# central_sensoresv7.net
KiCad netlist of a schematic drawn in EAGLE
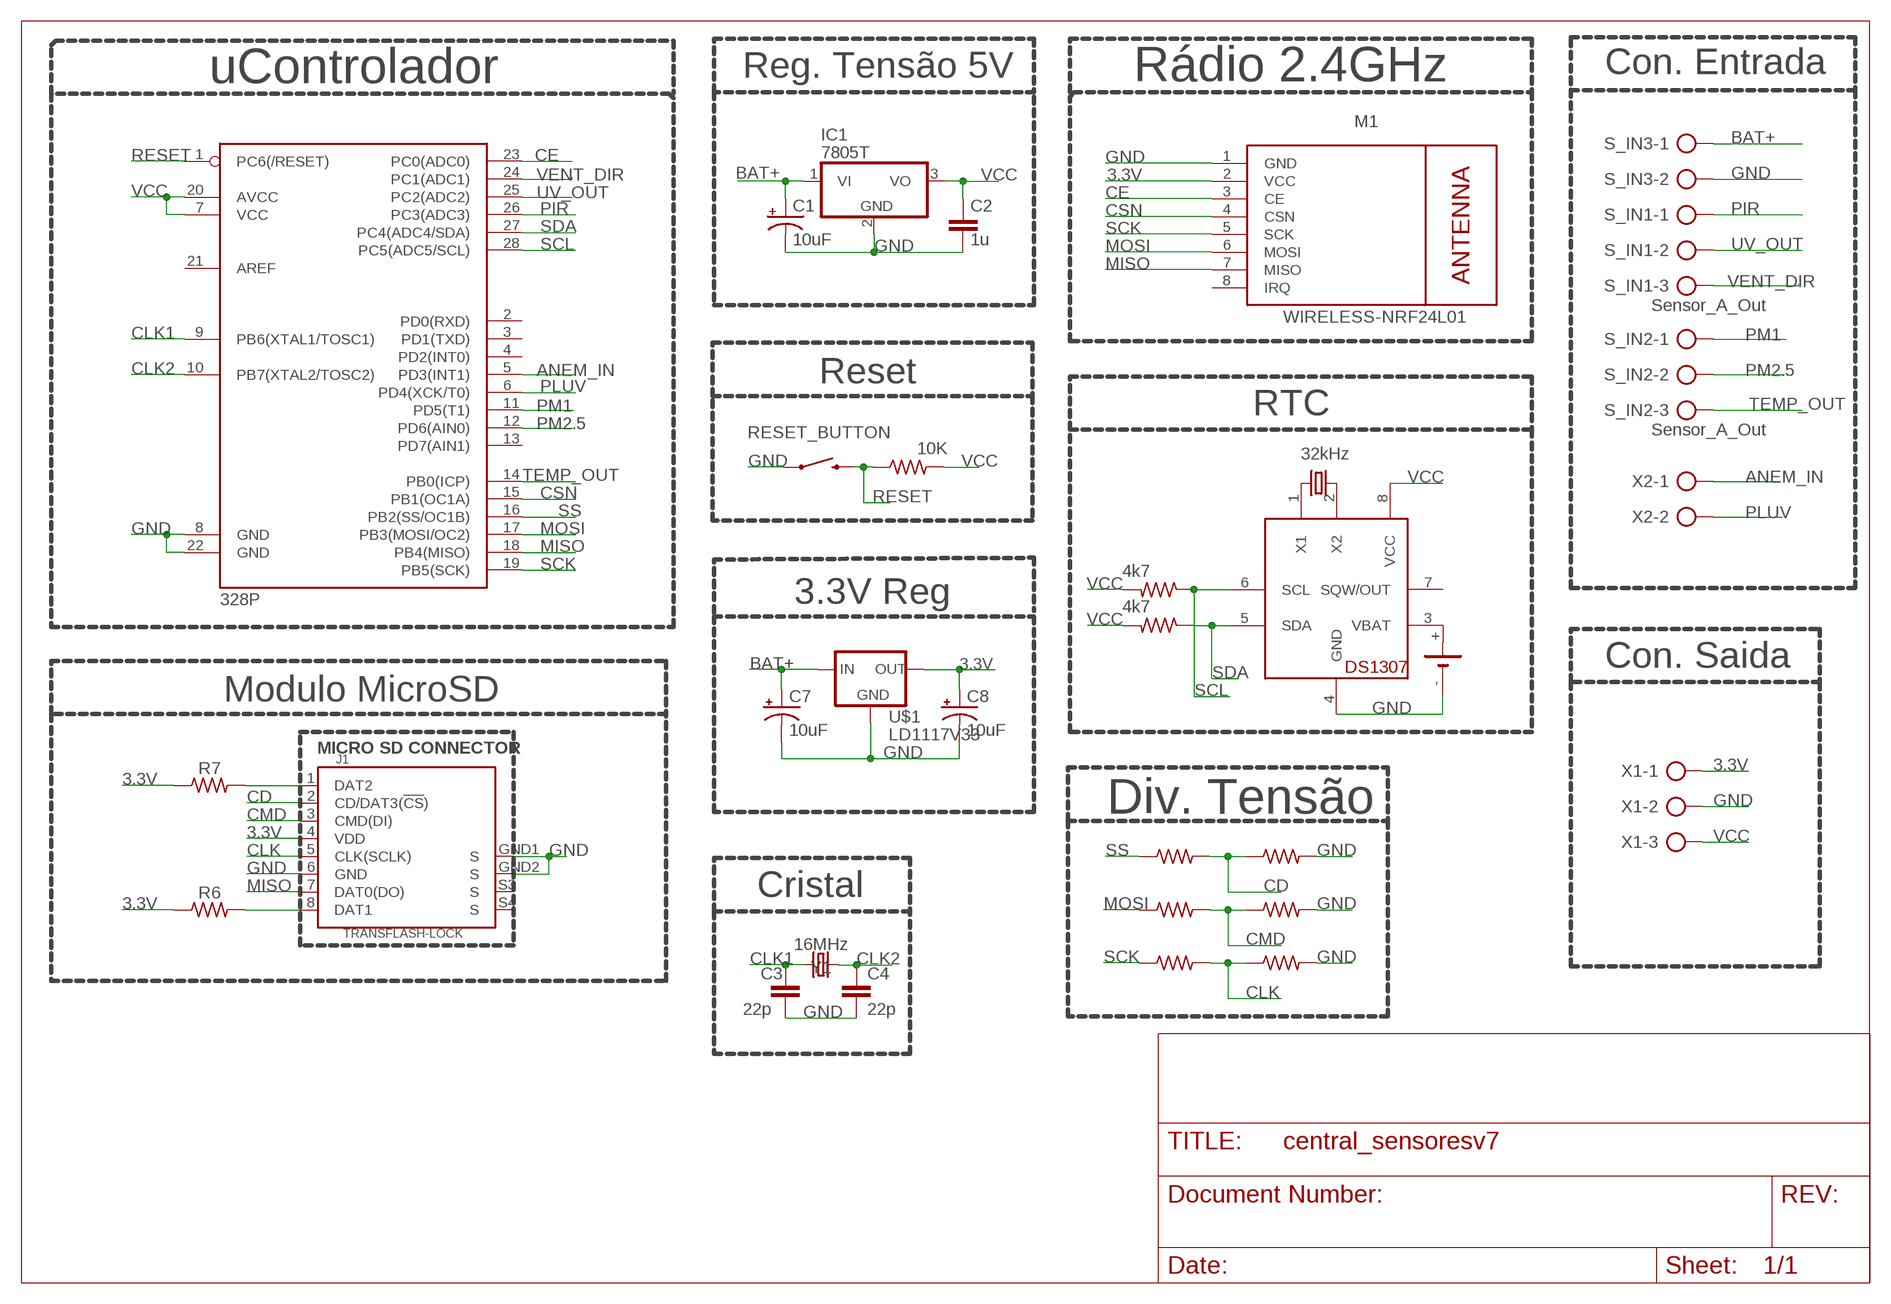
[diagram p0: schematic, sheet 1]

(export (version "E")
  (design (tool "Eeschema 10.0.6"))
  (components
    (comp (ref "C1")
      (value "10uF")
      (footprint "eagle-import:CPOL-RADIAL-2.5MM-5MM")
      (libsource (lib "eagle-import") (part "10UF-POLAR-RADIAL-2.5MM-25V-20%"))
    )
    (comp (ref "C2")
      (value "1u")
      (footprint "eagle-import:C025-024X044")
      (libsource (lib "eagle-import") (part "C-EU025-024X044"))
    )
    (comp (ref "C3")
      (value "22p")
      (footprint "eagle-import:C2.5-3")
      (libsource (lib "eagle-import") (part "C2,5-3"))
    )
    (comp (ref "C4")
      (value "22p")
      (footprint "eagle-import:C2.5-3")
      (libsource (lib "eagle-import") (part "C2,5-3"))
    )
    (comp (ref "C7")
      (value "10uF")
      (footprint "eagle-import:CPOL-RADIAL-2.5MM-5MM")
      (libsource (lib "eagle-import") (part "10UF-POLAR-RADIAL-2.5MM-25V-20%"))
    )
    (comp (ref "C8")
      (value "10uF")
      (footprint "eagle-import:CPOL-RADIAL-2.5MM-5MM")
      (libsource (lib "eagle-import") (part "10UF-POLAR-RADIAL-2.5MM-25V-20%"))
    )
    (comp (ref "G2")
      (value "CH291-1220LF")
      (footprint "eagle-import:CH291-1220LF")
      (libsource (lib "eagle-import") (part "CH291-1220LF"))
    )
    (comp (ref "IC1")
      (value "7805T")
      (footprint "eagle-import:TO220H")
      (libsource (lib "eagle-import") (part "78T05"))
    )
    (comp (ref "IC2")
      (value "DS1307")
      (footprint "eagle-import:DIL08")
      (libsource (lib "eagle-import") (part "DS1307"))
    )
    (comp (ref "J1")
      (value "TRANSFLASH-LOCK")
      (footprint "eagle-import:TRANSFLASH-LOCK-SOCK")
      (libsource (lib "eagle-import") (part "TRANSFLASH-LOCK"))
    )
    (comp (ref "M1")
      (value "WIRELESS-NRF24L01")
      (footprint "eagle-import:WIRELESS-NRF24L01")
      (libsource (lib "eagle-import") (part "WIRELESS-NRF24L01"))
    )
    (comp (ref "R1")
      (value "10K")
      (footprint "eagle-import:0204_7")
      (libsource (lib "eagle-import") (part "R-US_0204/7"))
    )
    (comp (ref "R2")
      (value "R-US_0204/7")
      (footprint "eagle-import:0204_7")
      (libsource (lib "eagle-import") (part "resistor_R-US_0204/7"))
    )
    (comp (ref "R3")
      (value "R-US_0204/7")
      (footprint "eagle-import:0204_7")
      (libsource (lib "eagle-import") (part "resistor_R-US_0204/7"))
    )
    (comp (ref "R4")
      (value "4k7")
      (footprint "eagle-import:0204_7")
      (libsource (lib "eagle-import") (part "R-US_0204/7"))
    )
    (comp (ref "R5")
      (value "4k7")
      (footprint "eagle-import:0204_7")
      (libsource (lib "eagle-import") (part "R-US_0204/7"))
    )
    (comp (ref "R6")
      (value "100k")
      (footprint "eagle-import:0204_7")
      (libsource (lib "eagle-import") (part "resistor_R-US_0204/7"))
    )
    (comp (ref "R7")
      (value "100k")
      (footprint "eagle-import:0204_7")
      (libsource (lib "eagle-import") (part "resistor_R-US_0204/7"))
    )
    (comp (ref "R8")
      (value "R-US_0204/7")
      (footprint "eagle-import:0204_7")
      (libsource (lib "eagle-import") (part "resistor_R-US_0204/7"))
    )
    (comp (ref "R9")
      (value "R-US_0204/7")
      (footprint "eagle-import:0204_7")
      (libsource (lib "eagle-import") (part "resistor_R-US_0204/7"))
    )
    (comp (ref "R10")
      (value "R-US_0204/7")
      (footprint "eagle-import:0204_7")
      (libsource (lib "eagle-import") (part "resistor_R-US_0204/7"))
    )
    (comp (ref "R11")
      (value "R-US_0204/7")
      (footprint "eagle-import:0204_7")
      (libsource (lib "eagle-import") (part "resistor_R-US_0204/7"))
    )
    (comp (ref "RESET_BUTTON")
      (value "MOMENTARY-SWITCH-SPST-PTH-6.0MM")
      (footprint "eagle-import:TACTILE_SWITCH_PTH_6.0MM")
      (libsource (lib "eagle-import") (part "MOMENTARY-SWITCH-SPST-PTH-6.0MM"))
    )
    (comp (ref "S_IN1")
      (value "Sensor_A_Out")
      (footprint "eagle-import:AK500_3-H")
      (libsource (lib "eagle-import") (part "AK500/3-H"))
    )
    (comp (ref "S_IN2")
      (value "Sensor_A_Out")
      (footprint "eagle-import:AK500_3-H")
      (libsource (lib "eagle-import") (part "AK500/3-H"))
    )
    (comp (ref "S_IN3")
      (value "Sensor_A_Out")
      (footprint "eagle-import:AK500_2-H")
      (libsource (lib "eagle-import") (part "AK500/2-H"))
    )
    (comp (ref "U$1")
      (value "LD1117V33")
      (footprint "eagle-import:LD1117V33")
      (libsource (lib "eagle-import") (part "LD1117V33"))
    )
    (comp (ref "U1")
      (value "328P")
      (footprint "eagle-import:DIP28")
      (libsource (lib "eagle-import") (part "ATMEGA328P_PDIP"))
    )
    (comp (ref "X1")
      (value "AK500/3-H")
      (footprint "eagle-import:AK500_3-H")
      (libsource (lib "eagle-import") (part "AK500/3-H"))
    )
    (comp (ref "X2")
      (value "AK500/2-H")
      (footprint "eagle-import:AK500_2-H")
      (libsource (lib "eagle-import") (part "AK500/2-H"))
    )
    (comp (ref "Y1")
      (value "16MHz")
      (footprint "eagle-import:HC49US")
      (libsource (lib "eagle-import") (part "CRYSTAL-16MHZPTH-HC49US"))
    )
    (comp (ref "Y2")
      (value "32kHz")
      (footprint "eagle-import:TC38H")
      (libsource (lib "eagle-import") (part "CRYSTALTC38H"))
    )
  )
  (nets
    (net (code "1") (name "/3.3V") (class "Default")
      (node (ref "C8") (pin "1") (pinfunction "+_1") (pintype "passive"))
      (node (ref "J1") (pin "4") (pinfunction "VDD_4") (pintype "power_in"))
      (node (ref "M1") (pin "2") (pinfunction "VCC_2") (pintype "power_in"))
      (node (ref "R6") (pin "1") (pinfunction "1_1") (pintype "passive"))
      (node (ref "R7") (pin "1") (pinfunction "1_1") (pintype "passive"))
      (node (ref "U$1") (pin "OUT") (pinfunction "OUT_OUT") (pintype "output"))
      (node (ref "X1") (pin "1") (pinfunction "KL_1") (pintype "passive"))
    )
    (net (code "2") (name "/ANEM_IN") (class "Default")
      (node (ref "U1") (pin "5") (pinfunction "PD3(INT1)_5") (pintype "bidirectional"))
      (node (ref "X2") (pin "1") (pinfunction "KL_1") (pintype "passive"))
    )
    (net (code "3") (name "/BAT+") (class "Default")
      (node (ref "C1") (pin "1") (pinfunction "+_1") (pintype "passive"))
      (node (ref "C7") (pin "1") (pinfunction "+_1") (pintype "passive"))
      (node (ref "IC1") (pin "1") (pinfunction "VI_1") (pintype "input"))
      (node (ref "S_IN3") (pin "1") (pinfunction "KL_1") (pintype "passive"))
      (node (ref "U$1") (pin "IN") (pinfunction "IN_IN") (pintype "input"))
    )
    (net (code "4") (name "/CD") (class "Default")
      (node (ref "J1") (pin "2") (pinfunction "CD/DAT3(~{CS})_2") (pintype "bidirectional"))
      (node (ref "R2") (pin "2") (pinfunction "2_2") (pintype "passive"))
      (node (ref "R3") (pin "1") (pinfunction "1_1") (pintype "passive"))
    )
    (net (code "5") (name "/CE") (class "Default")
      (node (ref "M1") (pin "3") (pinfunction "CE_3") (pintype "bidirectional"))
      (node (ref "U1") (pin "23") (pinfunction "PC0(ADC0)_23") (pintype "bidirectional"))
    )
    (net (code "6") (name "/CLK") (class "Default")
      (node (ref "J1") (pin "5") (pinfunction "CLK(SCLK)_5") (pintype "bidirectional"))
      (node (ref "R10") (pin "2") (pinfunction "2_2") (pintype "passive"))
      (node (ref "R11") (pin "1") (pinfunction "1_1") (pintype "passive"))
    )
    (net (code "7") (name "/CLK1") (class "Default")
      (node (ref "C3") (pin "1") (pinfunction "1_1") (pintype "passive"))
      (node (ref "U1") (pin "9") (pinfunction "PB6(XTAL1/TOSC1)_9") (pintype "bidirectional"))
      (node (ref "Y1") (pin "2") (pinfunction "2_2") (pintype "passive"))
    )
    (net (code "8") (name "/CLK2") (class "Default")
      (node (ref "C4") (pin "1") (pinfunction "1_1") (pintype "passive"))
      (node (ref "U1") (pin "10") (pinfunction "PB7(XTAL2/TOSC2)_10") (pintype "bidirectional"))
      (node (ref "Y1") (pin "1") (pinfunction "1_1") (pintype "passive"))
    )
    (net (code "9") (name "/CMD") (class "Default")
      (node (ref "J1") (pin "3") (pinfunction "CMD(DI)_3") (pintype "bidirectional"))
      (node (ref "R8") (pin "2") (pinfunction "2_2") (pintype "passive"))
      (node (ref "R9") (pin "1") (pinfunction "1_1") (pintype "passive"))
    )
    (net (code "10") (name "/CSN") (class "Default")
      (node (ref "M1") (pin "4") (pinfunction "CSN_4") (pintype "bidirectional"))
      (node (ref "U1") (pin "15") (pinfunction "PB1(OC1A)_15") (pintype "bidirectional"))
    )
    (net (code "11") (name "/GND") (class "Default")
      (node (ref "C1") (pin "2") (pinfunction "-_2") (pintype "passive"))
      (node (ref "C2") (pin "2") (pinfunction "2_2") (pintype "passive"))
      (node (ref "C3") (pin "2") (pinfunction "2_2") (pintype "passive"))
      (node (ref "C4") (pin "2") (pinfunction "2_2") (pintype "passive"))
      (node (ref "C7") (pin "2") (pinfunction "-_2") (pintype "passive"))
      (node (ref "C8") (pin "2") (pinfunction "-_2") (pintype "passive"))
      (node (ref "G2") (pin "-") (pinfunction "-_-") (pintype "passive"))
      (node (ref "IC1") (pin "2") (pinfunction "GND_2") (pintype "passive"))
      (node (ref "IC2") (pin "4") (pinfunction "GND_4") (pintype "power_in"))
      (node (ref "J1") (pin "6") (pinfunction "GND_6") (pintype "power_in"))
      (node (ref "J1") (pin "GND1") (pinfunction "S_GND1") (pintype "passive"))
      (node (ref "J1") (pin "GND2") (pinfunction "S_GND2") (pintype "passive"))
      (node (ref "M1") (pin "1") (pinfunction "GND_1") (pintype "power_in"))
      (node (ref "R11") (pin "2") (pinfunction "2_2") (pintype "passive"))
      (node (ref "R3") (pin "2") (pinfunction "2_2") (pintype "passive"))
      (node (ref "R9") (pin "2") (pinfunction "2_2") (pintype "passive"))
      (node (ref "RESET_BUTTON") (pin "1") (pinfunction "1_1") (pintype "passive"))
      (node (ref "S_IN3") (pin "2") (pinfunction "KL_2") (pintype "passive"))
      (node (ref "U$1") (pin "GND") (pinfunction "GND_GND") (pintype "input"))
      (node (ref "U1") (pin "22") (pinfunction "GND_22") (pintype "bidirectional"))
      (node (ref "U1") (pin "8") (pinfunction "GND_8") (pintype "bidirectional"))
      (node (ref "X1") (pin "2") (pinfunction "KL_2") (pintype "passive"))
    )
    (net (code "12") (name "/MISO") (class "Default")
      (node (ref "J1") (pin "7") (pinfunction "DAT0(DO)_7") (pintype "bidirectional"))
      (node (ref "M1") (pin "7") (pinfunction "MISO_7") (pintype "bidirectional"))
      (node (ref "U1") (pin "18") (pinfunction "PB4(MISO)_18") (pintype "bidirectional"))
    )
    (net (code "13") (name "/MOSI") (class "Default")
      (node (ref "M1") (pin "6") (pinfunction "MOSI_6") (pintype "bidirectional"))
      (node (ref "R8") (pin "1") (pinfunction "1_1") (pintype "passive"))
      (node (ref "U1") (pin "17") (pinfunction "PB3(MOSI/OC2)_17") (pintype "bidirectional"))
    )
    (net (code "14") (name "/PIR") (class "Default")
      (node (ref "S_IN1") (pin "1") (pinfunction "KL_1") (pintype "passive"))
      (node (ref "U1") (pin "26") (pinfunction "PC3(ADC3)_26") (pintype "bidirectional"))
    )
    (net (code "15") (name "/PLUV") (class "Default")
      (node (ref "U1") (pin "6") (pinfunction "PD4(XCK/T0)_6") (pintype "bidirectional"))
      (node (ref "X2") (pin "2") (pinfunction "KL_2") (pintype "passive"))
    )
    (net (code "16") (name "/PM1") (class "Default")
      (node (ref "S_IN2") (pin "1") (pinfunction "KL_1") (pintype "passive"))
      (node (ref "U1") (pin "11") (pinfunction "PD5(T1)_11") (pintype "bidirectional"))
    )
    (net (code "17") (name "/PM2.5") (class "Default")
      (node (ref "S_IN2") (pin "2") (pinfunction "KL_2") (pintype "passive"))
      (node (ref "U1") (pin "12") (pinfunction "PD6(AIN0)_12") (pintype "bidirectional"))
    )
    (net (code "18") (name "/RESET") (class "Default")
      (node (ref "R1") (pin "1") (pinfunction "1_1") (pintype "passive"))
      (node (ref "RESET_BUTTON") (pin "3") (pinfunction "2_3") (pintype "passive"))
      (node (ref "U1") (pin "1") (pinfunction "PC6(/RESET)_1") (pintype "bidirectional"))
    )
    (net (code "19") (name "/SCK") (class "Default")
      (node (ref "M1") (pin "5") (pinfunction "SCK_5") (pintype "bidirectional"))
      (node (ref "R10") (pin "1") (pinfunction "1_1") (pintype "passive"))
      (node (ref "U1") (pin "19") (pinfunction "PB5(SCK)_19") (pintype "bidirectional"))
    )
    (net (code "20") (name "/SCL") (class "Default")
      (node (ref "IC2") (pin "6") (pinfunction "SCL_6") (pintype "bidirectional"))
      (node (ref "R4") (pin "1") (pinfunction "1_1") (pintype "passive"))
      (node (ref "U1") (pin "28") (pinfunction "PC5(ADC5/SCL)_28") (pintype "bidirectional"))
    )
    (net (code "21") (name "/SDA") (class "Default")
      (node (ref "IC2") (pin "5") (pinfunction "SDA_5") (pintype "bidirectional"))
      (node (ref "R5") (pin "1") (pinfunction "1_1") (pintype "passive"))
      (node (ref "U1") (pin "27") (pinfunction "PC4(ADC4/SDA)_27") (pintype "bidirectional"))
    )
    (net (code "22") (name "/SS") (class "Default")
      (node (ref "R2") (pin "1") (pinfunction "1_1") (pintype "passive"))
      (node (ref "U1") (pin "16") (pinfunction "PB2(SS/OC1B)_16") (pintype "bidirectional"))
    )
    (net (code "23") (name "/TEMP_OUT") (class "Default")
      (node (ref "S_IN2") (pin "3") (pinfunction "KL_3") (pintype "passive"))
      (node (ref "U1") (pin "14") (pinfunction "PB0(ICP)_14") (pintype "bidirectional"))
    )
    (net (code "24") (name "/UV_OUT") (class "Default")
      (node (ref "S_IN1") (pin "2") (pinfunction "KL_2") (pintype "passive"))
      (node (ref "U1") (pin "25") (pinfunction "PC2(ADC2)_25") (pintype "bidirectional"))
    )
    (net (code "25") (name "/VCC") (class "Default")
      (node (ref "C2") (pin "1") (pinfunction "1_1") (pintype "passive"))
      (node (ref "IC1") (pin "3") (pinfunction "VO_3") (pintype "passive"))
      (node (ref "IC2") (pin "8") (pinfunction "VCC_8") (pintype "power_in"))
      (node (ref "R1") (pin "2") (pinfunction "2_2") (pintype "passive"))
      (node (ref "R4") (pin "2") (pinfunction "2_2") (pintype "passive"))
      (node (ref "R5") (pin "2") (pinfunction "2_2") (pintype "passive"))
      (node (ref "U1") (pin "20") (pinfunction "AVCC_20") (pintype "bidirectional"))
      (node (ref "U1") (pin "7") (pinfunction "VCC_7") (pintype "bidirectional"))
      (node (ref "X1") (pin "3") (pinfunction "KL_3") (pintype "passive"))
    )
    (net (code "26") (name "/VENT_DIR") (class "Default")
      (node (ref "S_IN1") (pin "3") (pinfunction "KL_3") (pintype "passive"))
      (node (ref "U1") (pin "24") (pinfunction "PC1(ADC1)_24") (pintype "bidirectional"))
    )
    (net (code "27") (name "Net-(IC2-VBAT)") (class "Default")
      (node (ref "G2") (pin "+") (pinfunction "+_+") (pintype "passive"))
      (node (ref "IC2") (pin "3") (pinfunction "VBAT_3") (pintype "power_in"))
    )
    (net (code "28") (name "Net-(IC2-X1)") (class "Default")
      (node (ref "IC2") (pin "1") (pinfunction "X1_1") (pintype "passive"))
      (node (ref "Y2") (pin "1") (pinfunction "1_1") (pintype "passive"))
    )
    (net (code "29") (name "Net-(IC2-X2)") (class "Default")
      (node (ref "IC2") (pin "2") (pinfunction "X2_2") (pintype "passive"))
      (node (ref "Y2") (pin "2") (pinfunction "2_2") (pintype "passive"))
    )
    (net (code "30") (name "Net-(J1-DAT1)") (class "Default")
      (node (ref "J1") (pin "8") (pinfunction "DAT1_8") (pintype "bidirectional"))
      (node (ref "R6") (pin "2") (pinfunction "2_2") (pintype "passive"))
    )
    (net (code "31") (name "Net-(J1-DAT2)") (class "Default")
      (node (ref "J1") (pin "1") (pinfunction "DAT2_1") (pintype "bidirectional"))
      (node (ref "R7") (pin "2") (pinfunction "2_2") (pintype "passive"))
    )
    (net (code "32") (name "unconnected-(IC2-SQW{slash}OUT-Pad7)") (class "Default")
      (node (ref "IC2") (pin "7") (pinfunction "SQW/OUT_7") (pintype "bidirectional"))
    )
    (net (code "33") (name "unconnected-(J1-S-PadS3)") (class "Default")
      (node (ref "J1") (pin "S3") (pinfunction "S_S3") (pintype "passive"))
    )
    (net (code "34") (name "unconnected-(J1-S-PadS4)") (class "Default")
      (node (ref "J1") (pin "S4") (pinfunction "S_S4") (pintype "passive"))
    )
    (net (code "35") (name "unconnected-(M1-IRQ-Pad8)") (class "Default")
      (node (ref "M1") (pin "8") (pinfunction "IRQ_8") (pintype "bidirectional"))
    )
    (net (code "36") (name "unconnected-(U1-AREF-Pad21)") (class "Default")
      (node (ref "U1") (pin "21") (pinfunction "AREF_21") (pintype "bidirectional"))
    )
    (net (code "37") (name "unconnected-(U1-PD0(RXD)-Pad2)") (class "Default")
      (node (ref "U1") (pin "2") (pinfunction "PD0(RXD)_2") (pintype "bidirectional"))
    )
    (net (code "38") (name "unconnected-(U1-PD1(TXD)-Pad3)") (class "Default")
      (node (ref "U1") (pin "3") (pinfunction "PD1(TXD)_3") (pintype "bidirectional"))
    )
    (net (code "39") (name "unconnected-(U1-PD2(INT0)-Pad4)") (class "Default")
      (node (ref "U1") (pin "4") (pinfunction "PD2(INT0)_4") (pintype "bidirectional"))
    )
    (net (code "40") (name "unconnected-(U1-PD7(AIN1)-Pad13)") (class "Default")
      (node (ref "U1") (pin "13") (pinfunction "PD7(AIN1)_13") (pintype "bidirectional"))
    )
  )
)
